# ir_single_long.net
KiCad netlist of a schematic drawn in EAGLE
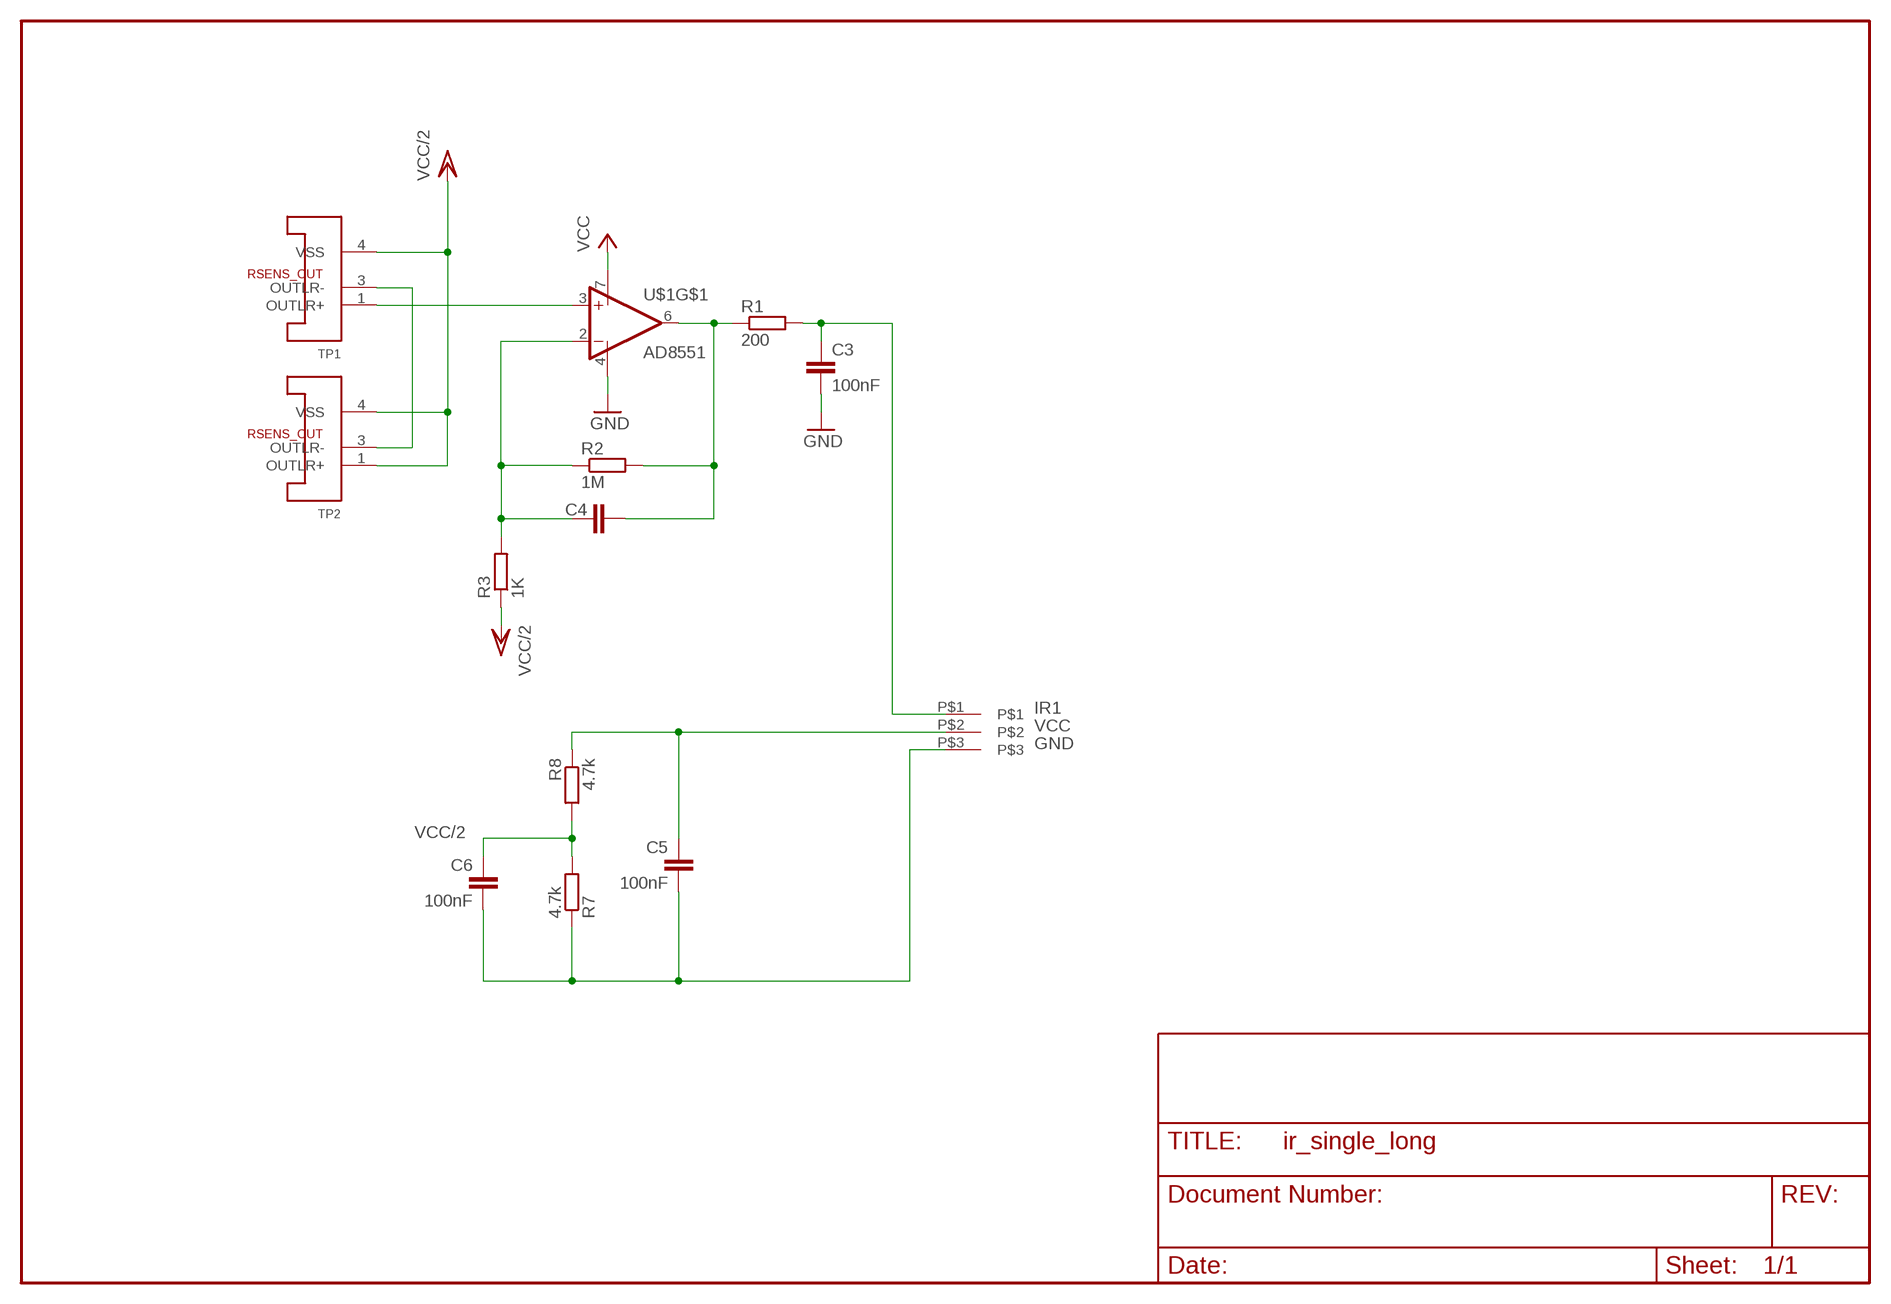
[diagram p0: schematic, sheet 1]

(export (version "E")
  (design (tool "Eeschema 10.0.6"))
  (components
    (comp (ref "C3")
      (value "100nF")
      (footprint "eagle-import:C1206K")
      (libsource (lib "eagle-import") (part "C-EUC1206K"))
    )
    (comp (ref "C4")
      (value "C-EUC0603")
      (footprint "eagle-import:C0603")
      (libsource (lib "eagle-import") (part "C-EUC0603"))
    )
    (comp (ref "C5")
      (value "100nF")
      (footprint "eagle-import:C0603")
      (libsource (lib "eagle-import") (part "C-EUC0603"))
    )
    (comp (ref "C6")
      (value "100nF")
      (footprint "eagle-import:C0603")
      (libsource (lib "eagle-import") (part "C-EUC0603"))
    )
    (comp (ref "R1")
      (value "200")
      (footprint "eagle-import:R0603")
      (libsource (lib "eagle-import") (part "R-EU_R0603"))
    )
    (comp (ref "R2")
      (value "1M")
      (footprint "eagle-import:R0603")
      (libsource (lib "eagle-import") (part "R-EU_R0603"))
    )
    (comp (ref "R3")
      (value "1K")
      (footprint "eagle-import:R0603")
      (libsource (lib "eagle-import") (part "R-EU_R0603"))
    )
    (comp (ref "R7")
      (value "4.7k")
      (footprint "eagle-import:R0603")
      (libsource (lib "eagle-import") (part "R-EU_R0603"))
    )
    (comp (ref "R8")
      (value "4.7k")
      (footprint "eagle-import:R0603")
      (libsource (lib "eagle-import") (part "R-EU_R0603"))
    )
    (comp (ref "TP1")
      (value "MLX90247SMD_LONG")
      (footprint "eagle-import:T0_39_SMD_LONG")
      (libsource (lib "eagle-import") (part "MLX90247SMD_LONG"))
    )
    (comp (ref "TP2")
      (value "MLX90247SMD_LONG")
      (footprint "eagle-import:T0_39_SMD_LONG")
      (libsource (lib "eagle-import") (part "MLX90247SMD_LONG"))
    )
    (comp (ref "U$1")
      (value "AD8551")
      (footprint "eagle-import:MSOP8")
      (libsource (lib "eagle-import") (part "AD8551"))
    )
    (comp (ref "U$2")
      (value "SOLD_PAD_3")
      (footprint "eagle-import:SOLD_PAD_2MM_3")
      (libsource (lib "eagle-import") (part "SOLD_PAD_3"))
    )
  )
  (nets
    (net (code "1") (name "/IR1") (class "Default")
      (node (ref "C3") (pin "1") (pinfunction "1_1") (pintype "passive"))
      (node (ref "R1") (pin "2") (pinfunction "2_2") (pintype "passive"))
      (node (ref "U$2") (pin "P$1") (pinfunction "P$1_P$1") (pintype "bidirectional"))
    )
    (net (code "2") (name "GND") (class "Default")
      (node (ref "C3") (pin "2") (pinfunction "2_2") (pintype "passive"))
      (node (ref "C5") (pin "2") (pinfunction "2_2") (pintype "passive"))
      (node (ref "C6") (pin "2") (pinfunction "2_2") (pintype "passive"))
      (node (ref "R7") (pin "1") (pinfunction "1_1") (pintype "passive"))
      (node (ref "U$1") (pin "4") (pinfunction "V-_4") (pintype "power_in"))
      (node (ref "U$2") (pin "P$3") (pinfunction "P$3_P$3") (pintype "bidirectional"))
    )
    (net (code "3") (name "Net-(TP1-OUTLR+)") (class "Default")
      (node (ref "TP1") (pin "1") (pinfunction "OUTLR+_1") (pintype "bidirectional"))
      (node (ref "U$1") (pin "3") (pinfunction "+IN_3") (pintype "input"))
    )
    (net (code "4") (name "Net-(TP1-OUTLR-)") (class "Default")
      (node (ref "TP1") (pin "3") (pinfunction "OUTLR-_3") (pintype "bidirectional"))
      (node (ref "TP2") (pin "3") (pinfunction "OUTLR-_3") (pintype "bidirectional"))
    )
    (net (code "5") (name "Net-(U$1A--IN)") (class "Default")
      (node (ref "C4") (pin "1") (pinfunction "1_1") (pintype "passive"))
      (node (ref "R2") (pin "1") (pinfunction "1_1") (pintype "passive"))
      (node (ref "R3") (pin "2") (pinfunction "2_2") (pintype "passive"))
      (node (ref "U$1") (pin "2") (pinfunction "-IN_2") (pintype "input"))
    )
    (net (code "6") (name "Net-(U$1A-OUT)") (class "Default")
      (node (ref "C4") (pin "2") (pinfunction "2_2") (pintype "passive"))
      (node (ref "R1") (pin "1") (pinfunction "1_1") (pintype "passive"))
      (node (ref "R2") (pin "2") (pinfunction "2_2") (pintype "passive"))
      (node (ref "U$1") (pin "6") (pinfunction "OUT_6") (pintype "output"))
    )
    (net (code "7") (name "VCC") (class "Default")
      (node (ref "C5") (pin "1") (pinfunction "1_1") (pintype "passive"))
      (node (ref "R8") (pin "1") (pinfunction "1_1") (pintype "passive"))
      (node (ref "U$1") (pin "7") (pinfunction "V+_7") (pintype "power_in"))
      (node (ref "U$2") (pin "P$2") (pinfunction "P$2_P$2") (pintype "bidirectional"))
    )
    (net (code "8") (name "VCC{slash}2") (class "Default")
      (node (ref "C6") (pin "1") (pinfunction "1_1") (pintype "passive"))
      (node (ref "R3") (pin "1") (pinfunction "1_1") (pintype "passive"))
      (node (ref "R7") (pin "2") (pinfunction "2_2") (pintype "passive"))
      (node (ref "R8") (pin "2") (pinfunction "2_2") (pintype "passive"))
      (node (ref "TP1") (pin "4") (pinfunction "VSS_4") (pintype "bidirectional"))
      (node (ref "TP2") (pin "1") (pinfunction "OUTLR+_1") (pintype "bidirectional"))
      (node (ref "TP2") (pin "4") (pinfunction "VSS_4") (pintype "bidirectional"))
    )
  )
)
